# photon-controller-v2.net
KiCad netlist of a schematic drawn in EAGLE
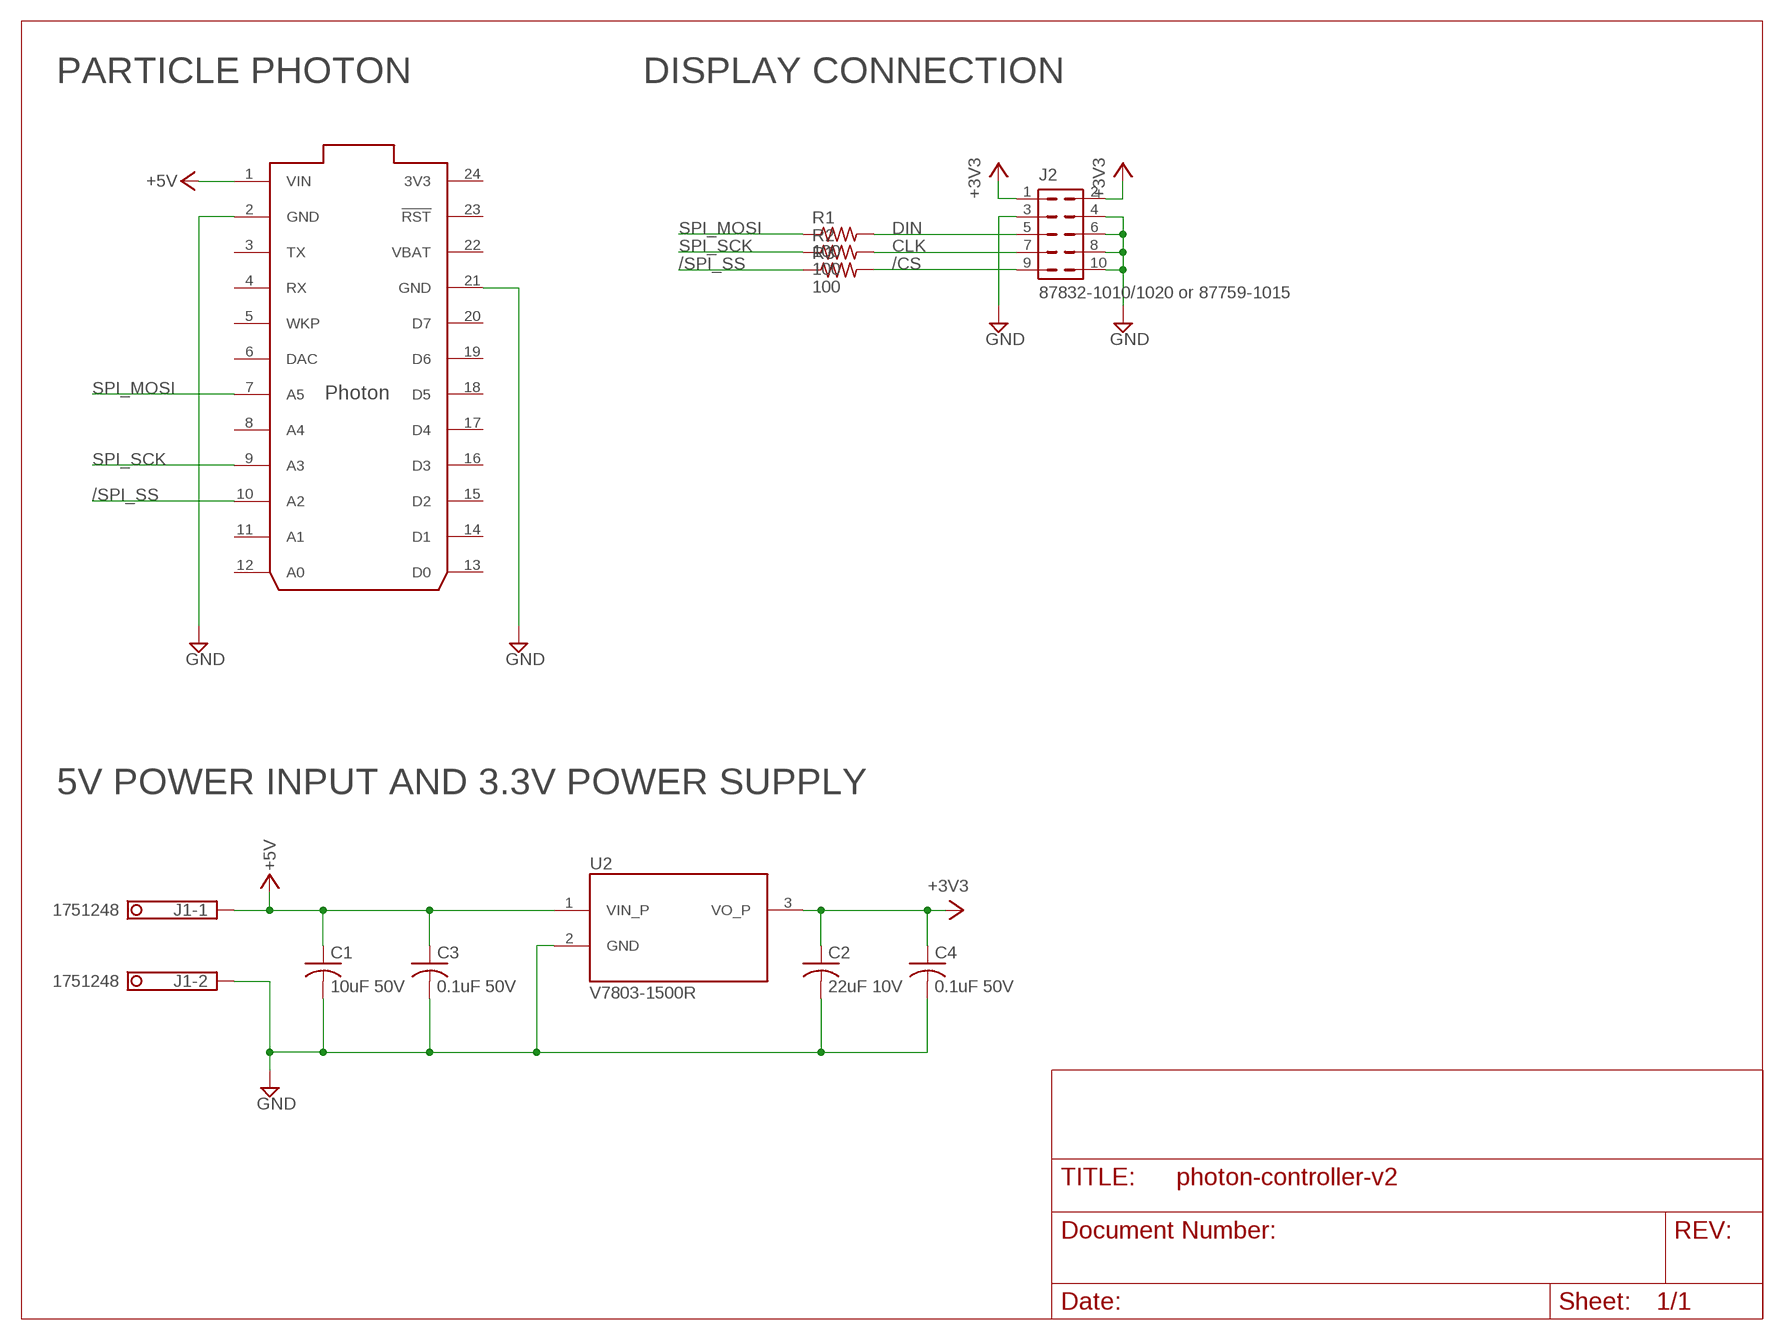
[diagram p0: schematic, sheet 1]

(export (version "E")
  (design (tool "Eeschema 10.0.6"))
  (components
    (comp (ref "C1")
      (value "10uF 50V")
      (footprint "eagle-import:C1210K")
      (fields (field (name "MFR") "KEMET") (field (name "MFR_PART_NO") "C1210C106K5RACTU"))
      (libsource (lib "eagle-import") (part "C-USC1210K"))
    )
    (comp (ref "C2")
      (value "22uF 10V")
      (footprint "eagle-import:C1206K")
      (fields (field (name "MFR") "KEMET") (field (name "MFR_PART_NO") "C1206C226K8RAC7800"))
      (libsource (lib "eagle-import") (part "C-USC1206K"))
    )
    (comp (ref "C3")
      (value "0.1uF 50V")
      (footprint "eagle-import:C1206K")
      (fields (field (name "MFR") "KEMET") (field (name "MFR_PART_NO") "C1206S104M5RACTU"))
      (libsource (lib "eagle-import") (part "C-USC1206K"))
    )
    (comp (ref "C4")
      (value "0.1uF 50V")
      (footprint "eagle-import:C1206K")
      (fields (field (name "MFR") "KEMET") (field (name "MFR_PART_NO") "C1206S104M5RACTU"))
      (libsource (lib "eagle-import") (part "C-USC1206K"))
    )
    (comp (ref "J1")
      (value "1751248")
      (footprint "eagle-import:1751248")
      (libsource (lib "eagle-import") (part "1751248"))
    )
    (comp (ref "J2")
      (value "87832-1010/1020 or 87759-1015")
      (footprint "eagle-import:87832-10")
      (libsource (lib "eagle-import") (part "87832-10"))
    )
    (comp (ref "R1")
      (value "100")
      (footprint "eagle-import:R1206")
      (libsource (lib "eagle-import") (part "R-US_R1206"))
    )
    (comp (ref "R2")
      (value "100")
      (footprint "eagle-import:R1206")
      (libsource (lib "eagle-import") (part "R-US_R1206"))
    )
    (comp (ref "R3")
      (value "100")
      (footprint "eagle-import:R1206")
      (libsource (lib "eagle-import") (part "R-US_R1206"))
    )
    (comp (ref "U1")
      (value "PHOTON_WITH_HEADERS")
      (footprint "eagle-import:PHOTON")
      (libsource (lib "eagle-import") (part "PHOTON_WITH_HEADERS"))
    )
    (comp (ref "U2")
      (value "V7803-1500R")
      (footprint "eagle-import:CONV_V7803-1500R")
      (fields (field (name "MANUFACTURER") "CUI INC"))
      (libsource (lib "eagle-import") (part "V7803-1500R"))
    )
  )
  (nets
    (net (code "1") (name "+3V3") (class "Default")
      (node (ref "C2") (pin "1") (pinfunction "1_1") (pintype "passive"))
      (node (ref "C4") (pin "1") (pinfunction "1_1") (pintype "passive"))
      (node (ref "J2") (pin "1") (pinfunction "1_1") (pintype "passive"))
      (node (ref "J2") (pin "2") (pinfunction "2_2") (pintype "passive"))
      (node (ref "U2") (pin "3") (pinfunction "VO_P_3") (pintype "output"))
    )
    (net (code "2") (name "+5V") (class "Default")
      (node (ref "C1") (pin "1") (pinfunction "1_1") (pintype "passive"))
      (node (ref "C3") (pin "1") (pinfunction "1_1") (pintype "passive"))
      (node (ref "J1") (pin "1") (pinfunction "K_1") (pintype "passive"))
      (node (ref "U1") (pin "1") (pinfunction "VIN_1") (pintype "power_in"))
      (node (ref "U2") (pin "1") (pinfunction "VIN_P_1") (pintype "input"))
    )
    (net (code "3") (name "/3V3") (class "Default")
      (node (ref "U1") (pin "24") (pinfunction "3V3_24") (pintype "power_in"))
    )
    (net (code "4") (name "/CLK") (class "Default")
      (node (ref "J2") (pin "7") (pinfunction "7_7") (pintype "passive"))
      (node (ref "R2") (pin "2") (pinfunction "2_2") (pintype "passive"))
    )
    (net (code "5") (name "/DIN") (class "Default")
      (node (ref "J2") (pin "5") (pinfunction "5_5") (pintype "passive"))
      (node (ref "R1") (pin "2") (pinfunction "2_2") (pintype "passive"))
    )
    (net (code "6") (name "/SPI_MOSI") (class "Default")
      (node (ref "R1") (pin "1") (pinfunction "1_1") (pintype "passive"))
      (node (ref "U1") (pin "7") (pinfunction "A5_7") (pintype "bidirectional"))
    )
    (net (code "7") (name "/SPI_SCK") (class "Default")
      (node (ref "R2") (pin "1") (pinfunction "1_1") (pintype "passive"))
      (node (ref "U1") (pin "9") (pinfunction "A3_9") (pintype "bidirectional"))
    )
    (net (code "8") (name "/VBAT") (class "Default")
      (node (ref "U1") (pin "22") (pinfunction "VBAT_22") (pintype "power_in"))
    )
    (net (code "9") (name "/{slash}CS") (class "Default")
      (node (ref "J2") (pin "9") (pinfunction "9_9") (pintype "passive"))
      (node (ref "R3") (pin "2") (pinfunction "2_2") (pintype "passive"))
    )
    (net (code "10") (name "/{slash}SPI_SS") (class "Default")
      (node (ref "R3") (pin "1") (pinfunction "1_1") (pintype "passive"))
      (node (ref "U1") (pin "10") (pinfunction "A2_10") (pintype "bidirectional"))
    )
    (net (code "11") (name "GND") (class "Default")
      (node (ref "C1") (pin "2") (pinfunction "2_2") (pintype "passive"))
      (node (ref "C2") (pin "2") (pinfunction "2_2") (pintype "passive"))
      (node (ref "C3") (pin "2") (pinfunction "2_2") (pintype "passive"))
      (node (ref "C4") (pin "2") (pinfunction "2_2") (pintype "passive"))
      (node (ref "J1") (pin "2") (pinfunction "K_2") (pintype "passive"))
      (node (ref "J2") (pin "10") (pinfunction "10_10") (pintype "passive"))
      (node (ref "J2") (pin "3") (pinfunction "3_3") (pintype "passive"))
      (node (ref "J2") (pin "4") (pinfunction "4_4") (pintype "passive"))
      (node (ref "J2") (pin "6") (pinfunction "6_6") (pintype "passive"))
      (node (ref "J2") (pin "8") (pinfunction "8_8") (pintype "passive"))
      (node (ref "U1") (pin "2") (pinfunction "GND_2") (pintype "power_in"))
      (node (ref "U1") (pin "21") (pinfunction "GND_21") (pintype "power_in"))
      (node (ref "U2") (pin "2") (pinfunction "GND_2") (pintype "power_in"))
    )
    (net (code "12") (name "unconnected-(U1-A0-Pad12)") (class "Default")
      (node (ref "U1") (pin "12") (pinfunction "A0_12") (pintype "bidirectional"))
    )
    (net (code "13") (name "unconnected-(U1-A1-Pad11)") (class "Default")
      (node (ref "U1") (pin "11") (pinfunction "A1_11") (pintype "bidirectional"))
    )
    (net (code "14") (name "unconnected-(U1-A4-Pad8)") (class "Default")
      (node (ref "U1") (pin "8") (pinfunction "A4_8") (pintype "bidirectional"))
    )
    (net (code "15") (name "unconnected-(U1-D0-Pad13)") (class "Default")
      (node (ref "U1") (pin "13") (pinfunction "D0_13") (pintype "bidirectional"))
    )
    (net (code "16") (name "unconnected-(U1-D1-Pad14)") (class "Default")
      (node (ref "U1") (pin "14") (pinfunction "D1_14") (pintype "bidirectional"))
    )
    (net (code "17") (name "unconnected-(U1-D2-Pad15)") (class "Default")
      (node (ref "U1") (pin "15") (pinfunction "D2_15") (pintype "bidirectional"))
    )
    (net (code "18") (name "unconnected-(U1-D3-Pad16)") (class "Default")
      (node (ref "U1") (pin "16") (pinfunction "D3_16") (pintype "bidirectional"))
    )
    (net (code "19") (name "unconnected-(U1-D4-Pad17)") (class "Default")
      (node (ref "U1") (pin "17") (pinfunction "D4_17") (pintype "bidirectional"))
    )
    (net (code "20") (name "unconnected-(U1-D5-Pad18)") (class "Default")
      (node (ref "U1") (pin "18") (pinfunction "D5_18") (pintype "bidirectional"))
    )
    (net (code "21") (name "unconnected-(U1-D6-Pad19)") (class "Default")
      (node (ref "U1") (pin "19") (pinfunction "D6_19") (pintype "bidirectional"))
    )
    (net (code "22") (name "unconnected-(U1-D7-Pad20)") (class "Default")
      (node (ref "U1") (pin "20") (pinfunction "D7_20") (pintype "bidirectional"))
    )
    (net (code "23") (name "unconnected-(U1-DAC-Pad6)") (class "Default")
      (node (ref "U1") (pin "6") (pinfunction "DAC_6") (pintype "bidirectional"))
    )
    (net (code "24") (name "unconnected-(U1-RX-Pad4)") (class "Default")
      (node (ref "U1") (pin "4") (pinfunction "RX_4") (pintype "bidirectional"))
    )
    (net (code "25") (name "unconnected-(U1-TX-Pad3)") (class "Default")
      (node (ref "U1") (pin "3") (pinfunction "TX_3") (pintype "bidirectional"))
    )
    (net (code "26") (name "unconnected-(U1-WKP-Pad5)") (class "Default")
      (node (ref "U1") (pin "5") (pinfunction "WKP_5") (pintype "bidirectional"))
    )
    (net (code "27") (name "unconnected-(U1-~{RST}-Pad23)") (class "Default")
      (node (ref "U1") (pin "23") (pinfunction "~{RST}_23") (pintype "bidirectional"))
    )
  )
)
